# Power_Supply_3_3V.net
KiCad netlist of a schematic drawn in EAGLE
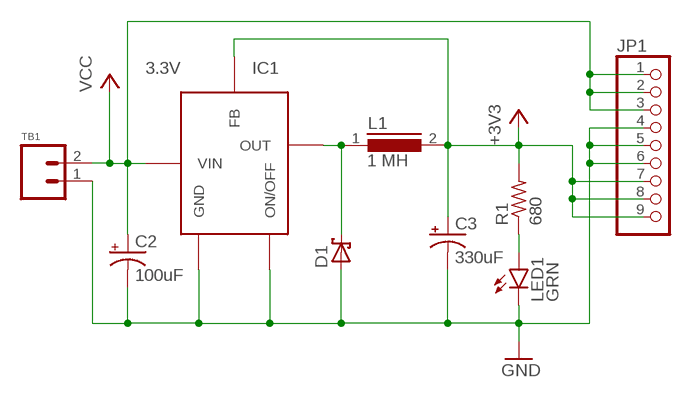
[diagram p0: schematic, sheet 1]

(export (version "E")
  (design (tool "Eeschema 10.0.6"))
  (components
    (comp (ref "C2")
      (value "100uF")
      (footprint "eagle-import:F_CAP")
      (libsource (lib "eagle-import") (part "CAP_POLF"))
    )
    (comp (ref "C3")
      (value "330uF")
      (footprint "eagle-import:F_CAP")
      (libsource (lib "eagle-import") (part "CAP_POLF"))
    )
    (comp (ref "D1")
      (value "SCHOTTKY_DIODE")
      (footprint "eagle-import:SMD_DIODE")
      (fields (field (name "MANF") "Diodes Inc"))
      (libsource (lib "eagle-import") (part "SCHOTTKY_DIODE"))
    )
    (comp (ref "IC1")
      (value "3.3V")
      (footprint "eagle-import:TO-263-5")
      (fields (field (name "MANF") "Texas Instruments"))
      (libsource (lib "eagle-import") (part "TL2575"))
    )
    (comp (ref "JP1")
      (value "PINHD-1X9")
      (footprint "eagle-import:1X09")
      (libsource (lib "eagle-import") (part "PINHD-1X9"))
    )
    (comp (ref "L1")
      (value "1 MH")
      (footprint "eagle-import:DR125")
      (fields (field (name "MANF") "Bourns Inc."))
      (libsource (lib "eagle-import") (part "DR125"))
    )
    (comp (ref "LED1")
      (value "GRN")
      (footprint "eagle-import:0603_LED")
      (fields (field (name "MANF") "Avago Technologies"))
      (libsource (lib "eagle-import") (part "LED0603"))
    )
    (comp (ref "R1")
      (value "680")
      (footprint "eagle-import:0603_RESISTOR")
      (libsource (lib "eagle-import") (part "RESISTOR0603"))
    )
    (comp (ref "TB1")
      (value "TERMINAL_BLOCK_2")
      (footprint "eagle-import:TERMINAL_BLOCK_2")
      (fields (field (name "MANF") "Phoenix"))
      (libsource (lib "eagle-import") (part "TERMINAL_BLOCK_2"))
    )
  )
  (nets
    (net (code "1") (name "+3V3") (class "Default")
      (node (ref "C3") (pin "+") (pinfunction "+_+") (pintype "passive"))
      (node (ref "IC1") (pin "4") (pinfunction "FB_4") (pintype "input"))
      (node (ref "JP1") (pin "7") (pinfunction "7_7") (pintype "passive"))
      (node (ref "JP1") (pin "8") (pinfunction "8_8") (pintype "passive"))
      (node (ref "JP1") (pin "9") (pinfunction "9_9") (pintype "passive"))
      (node (ref "L1") (pin "2") (pinfunction "2_2") (pintype "passive"))
      (node (ref "R1") (pin "2") (pinfunction "2_2") (pintype "passive"))
    )
    (net (code "2") (name "GND") (class "Default")
      (node (ref "C2") (pin "-") (pinfunction "-_-") (pintype "passive"))
      (node (ref "C3") (pin "-") (pinfunction "-_-") (pintype "passive"))
      (node (ref "D1") (pin "A") (pinfunction "A_A") (pintype "passive"))
      (node (ref "IC1") (pin "3") (pinfunction "GND_3") (pintype "power_in"))
      (node (ref "IC1") (pin "5") (pinfunction "ON/OFF_5") (pintype "input"))
      (node (ref "JP1") (pin "4") (pinfunction "4_4") (pintype "passive"))
      (node (ref "JP1") (pin "5") (pinfunction "5_5") (pintype "passive"))
      (node (ref "JP1") (pin "6") (pinfunction "6_6") (pintype "passive"))
      (node (ref "LED1") (pin "C") (pinfunction "C_C") (pintype "passive"))
      (node (ref "TB1") (pin "1") (pinfunction "1_1") (pintype "passive"))
    )
    (net (code "3") (name "Net-(IC1-OUT)") (class "Default")
      (node (ref "D1") (pin "C") (pinfunction "C_C") (pintype "passive"))
      (node (ref "IC1") (pin "2") (pinfunction "OUT_2") (pintype "power_in"))
      (node (ref "L1") (pin "1") (pinfunction "1_1") (pintype "passive"))
    )
    (net (code "4") (name "Net-(LED1-PadA)") (class "Default")
      (node (ref "LED1") (pin "A") (pinfunction "A_A") (pintype "passive"))
      (node (ref "R1") (pin "1") (pinfunction "1_1") (pintype "passive"))
    )
    (net (code "5") (name "VCC") (class "Default")
      (node (ref "C2") (pin "+") (pinfunction "+_+") (pintype "passive"))
      (node (ref "IC1") (pin "1") (pinfunction "VIN_1") (pintype "power_in"))
      (node (ref "JP1") (pin "1") (pinfunction "1_1") (pintype "passive"))
      (node (ref "JP1") (pin "2") (pinfunction "2_2") (pintype "passive"))
      (node (ref "JP1") (pin "3") (pinfunction "3_3") (pintype "passive"))
      (node (ref "TB1") (pin "2") (pinfunction "2_2") (pintype "passive"))
    )
  )
)
